# Custom_DUE.net
KiCad netlist of a schematic drawn in EAGLE
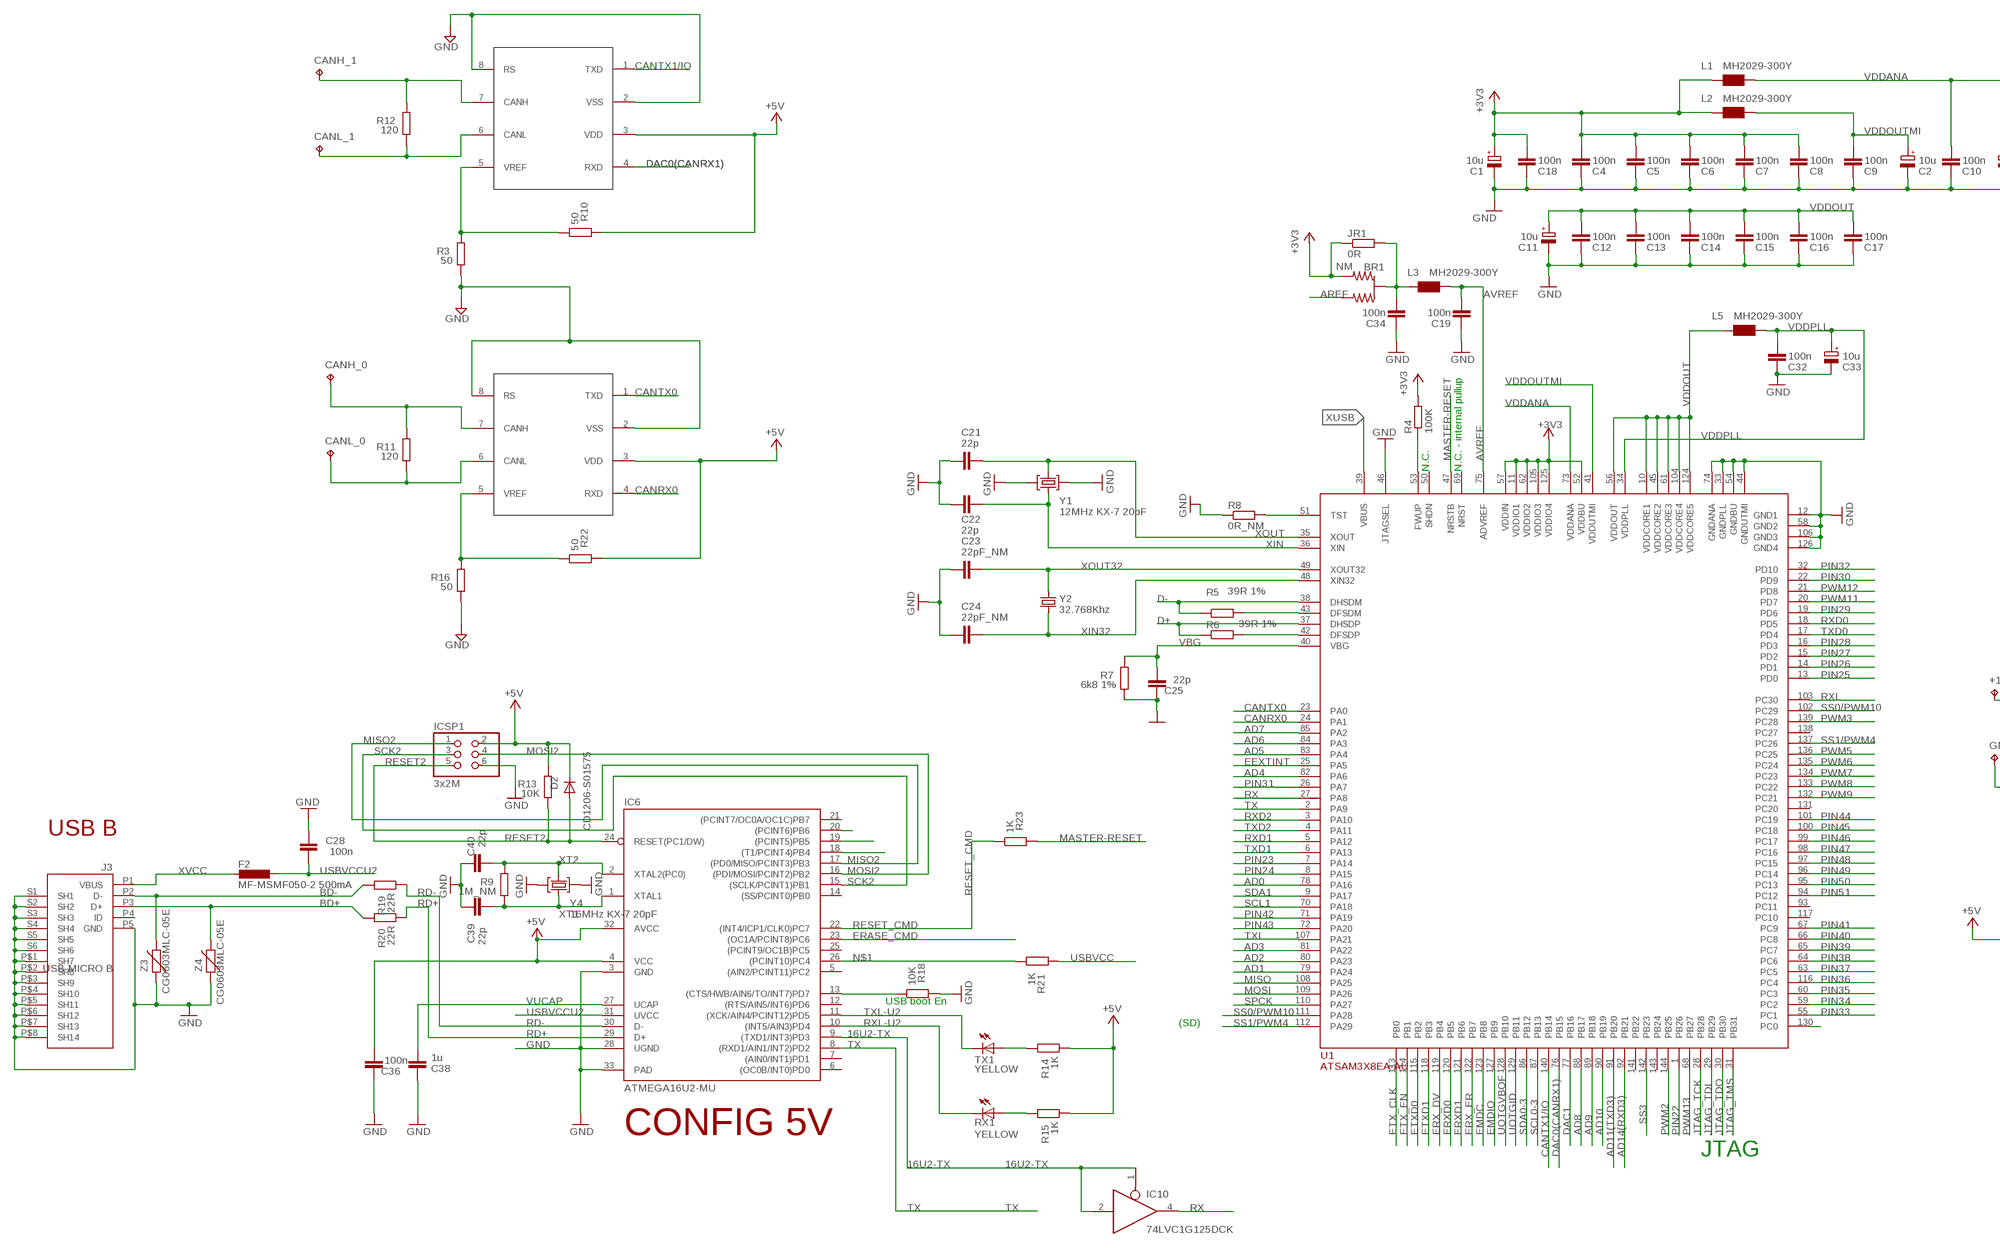
[diagram p0: schematic, sheet 1, part 1 of 2]
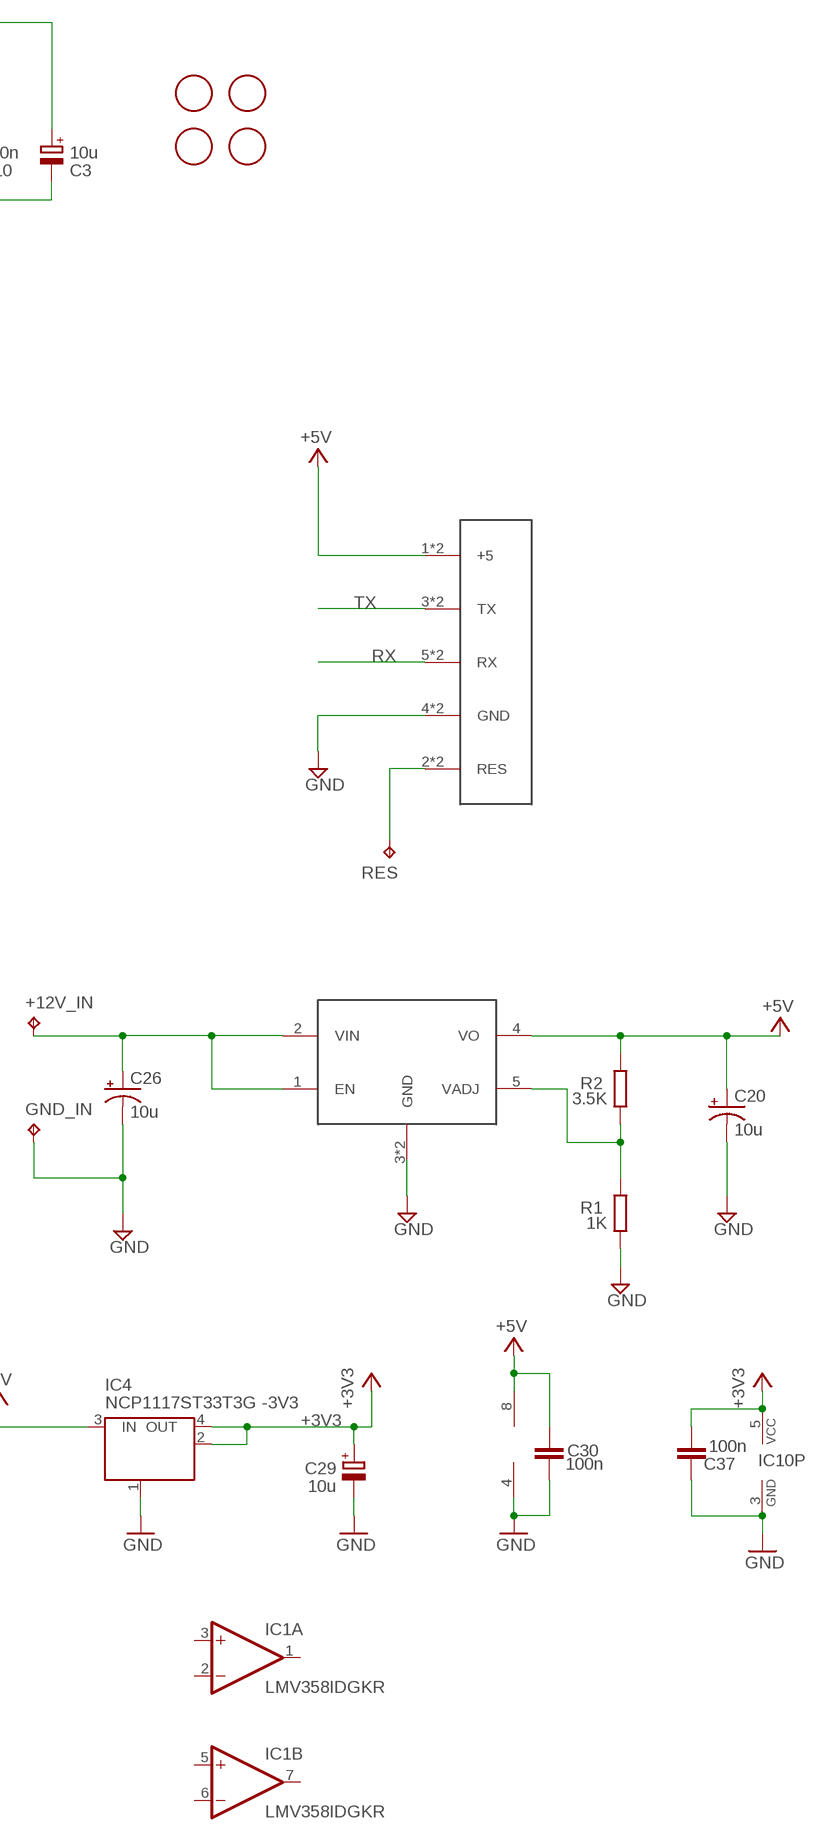
[diagram p1: schematic, sheet 1, part 2 of 2]

(export (version "E")
  (design (tool "Eeschema 10.0.6"))
  (components
    (comp (ref "+12V_IN")
      (value "TPPAD1-20")
      (footprint "eagle-import:P1-20")
      (libsource (lib "eagle-import") (part "TPPAD1-20"))
    )
    (comp (ref "BR1")
      (value "NM")
      (footprint "eagle-import:J0402")
      (libsource (lib "eagle-import") (part "J0402"))
    )
    (comp (ref "C1")
      (value "10u")
      (footprint "eagle-import:SMC_B")
      (libsource (lib "eagle-import") (part "CPOL-EUSMCB"))
    )
    (comp (ref "C2")
      (value "10u")
      (footprint "eagle-import:SMC_B")
      (libsource (lib "eagle-import") (part "CPOL-EUSMCB"))
    )
    (comp (ref "C3")
      (value "10u")
      (footprint "eagle-import:SMC_B")
      (libsource (lib "eagle-import") (part "CPOL-EUSMCB"))
    )
    (comp (ref "C4")
      (value "100n")
      (footprint "eagle-import:C0402")
      (libsource (lib "eagle-import") (part "C-EUC0402"))
    )
    (comp (ref "C5")
      (value "100n")
      (footprint "eagle-import:C0402")
      (libsource (lib "eagle-import") (part "C-EUC0402"))
    )
    (comp (ref "C6")
      (value "100n")
      (footprint "eagle-import:C0402")
      (libsource (lib "eagle-import") (part "C-EUC0402"))
    )
    (comp (ref "C7")
      (value "100n")
      (footprint "eagle-import:C0402")
      (libsource (lib "eagle-import") (part "C-EUC0402"))
    )
    (comp (ref "C8")
      (value "100n")
      (footprint "eagle-import:C0402")
      (libsource (lib "eagle-import") (part "C-EUC0402"))
    )
    (comp (ref "C9")
      (value "100n")
      (footprint "eagle-import:C0402")
      (libsource (lib "eagle-import") (part "C-EUC0402"))
    )
    (comp (ref "C10")
      (value "100n")
      (footprint "eagle-import:C0402")
      (libsource (lib "eagle-import") (part "C-EUC0402"))
    )
    (comp (ref "C11")
      (value "10u")
      (footprint "eagle-import:SMC_B")
      (libsource (lib "eagle-import") (part "CPOL-EUSMCB"))
    )
    (comp (ref "C12")
      (value "100n")
      (footprint "eagle-import:C0402")
      (libsource (lib "eagle-import") (part "C-EUC0402"))
    )
    (comp (ref "C13")
      (value "100n")
      (footprint "eagle-import:C0402")
      (libsource (lib "eagle-import") (part "C-EUC0402"))
    )
    (comp (ref "C14")
      (value "100n")
      (footprint "eagle-import:C0402")
      (libsource (lib "eagle-import") (part "C-EUC0402"))
    )
    (comp (ref "C15")
      (value "100n")
      (footprint "eagle-import:C0402")
      (libsource (lib "eagle-import") (part "C-EUC0402"))
    )
    (comp (ref "C16")
      (value "100n")
      (footprint "eagle-import:C0402")
      (libsource (lib "eagle-import") (part "C-EUC0402"))
    )
    (comp (ref "C17")
      (value "100n")
      (footprint "eagle-import:C0402")
      (libsource (lib "eagle-import") (part "C-EUC0402"))
    )
    (comp (ref "C18")
      (value "100n")
      (footprint "eagle-import:C0402")
      (libsource (lib "eagle-import") (part "C-EUC0402"))
    )
    (comp (ref "C19")
      (value "100n")
      (footprint "eagle-import:C0402")
      (libsource (lib "eagle-import") (part "C-EUC0402"))
    )
    (comp (ref "C20")
      (value "10u")
      (footprint "eagle-import:153CLV-0405")
      (libsource (lib "eagle-import") (part "CPOL-US153CLV-0405"))
    )
    (comp (ref "C21")
      (value "22p")
      (footprint "eagle-import:C0402")
      (libsource (lib "eagle-import") (part "C-EUC0402"))
    )
    (comp (ref "C22")
      (value "22p")
      (footprint "eagle-import:C0402")
      (libsource (lib "eagle-import") (part "C-EUC0402"))
    )
    (comp (ref "C23")
      (value "22pF_NM")
      (footprint "eagle-import:C0402")
      (libsource (lib "eagle-import") (part "C-EUC0402"))
    )
    (comp (ref "C24")
      (value "22pF_NM")
      (footprint "eagle-import:C0402")
      (libsource (lib "eagle-import") (part "C-EUC0402"))
    )
    (comp (ref "C25")
      (value "22p")
      (footprint "eagle-import:C0402")
      (libsource (lib "eagle-import") (part "C-EUC0402"))
    )
    (comp (ref "C26")
      (value "10u")
      (footprint "eagle-import:153CLV-0405")
      (libsource (lib "eagle-import") (part "CPOL-US153CLV-0405"))
    )
    (comp (ref "C28")
      (value "100n")
      (footprint "eagle-import:C0402")
      (libsource (lib "eagle-import") (part "C-EUC0402"))
    )
    (comp (ref "C29")
      (value "10u")
      (footprint "eagle-import:SMC_B")
      (libsource (lib "eagle-import") (part "CPOL-EUSMCB"))
    )
    (comp (ref "C30")
      (value "100n")
      (footprint "eagle-import:C0402")
      (libsource (lib "eagle-import") (part "C-EUC0402"))
    )
    (comp (ref "C32")
      (value "100n")
      (footprint "eagle-import:C0402")
      (libsource (lib "eagle-import") (part "C-EUC0402"))
    )
    (comp (ref "C33")
      (value "10u")
      (footprint "eagle-import:SMC_B")
      (libsource (lib "eagle-import") (part "CPOL-EUSMCB"))
    )
    (comp (ref "C34")
      (value "100n")
      (footprint "eagle-import:C0402")
      (libsource (lib "eagle-import") (part "C-EUC0402"))
    )
    (comp (ref "C36")
      (value "100n")
      (footprint "eagle-import:C0402")
      (libsource (lib "eagle-import") (part "C-EUC0402"))
    )
    (comp (ref "C37")
      (value "100n")
      (footprint "eagle-import:C0402")
      (libsource (lib "eagle-import") (part "C-EUC0402"))
    )
    (comp (ref "C38")
      (value "1u")
      (footprint "eagle-import:C0402")
      (libsource (lib "eagle-import") (part "C-EUC0402"))
    )
    (comp (ref "C39")
      (value "22p")
      (footprint "eagle-import:C0402")
      (libsource (lib "eagle-import") (part "C-EUC0402"))
    )
    (comp (ref "C40")
      (value "22p")
      (footprint "eagle-import:C0402")
      (libsource (lib "eagle-import") (part "C-EUC0402"))
    )
    (comp (ref "CANH_0")
      (value "TPPAD1-20")
      (footprint "eagle-import:P1-20")
      (libsource (lib "eagle-import") (part "TPPAD1-20"))
    )
    (comp (ref "CANH_1")
      (value "TPPAD1-20")
      (footprint "eagle-import:P1-20")
      (libsource (lib "eagle-import") (part "TPPAD1-20"))
    )
    (comp (ref "CANL_0")
      (value "TPPAD1-20")
      (footprint "eagle-import:P1-20")
      (libsource (lib "eagle-import") (part "TPPAD1-20"))
    )
    (comp (ref "CANL_1")
      (value "TPPAD1-20")
      (footprint "eagle-import:P1-20")
      (libsource (lib "eagle-import") (part "TPPAD1-20"))
    )
    (comp (ref "D2")
      (value "CD1206-S01575")
      (footprint "eagle-import:MINIMELF")
      (libsource (lib "eagle-import") (part "DIODE-MINIMELF"))
    )
    (comp (ref "F2")
      (value "MF-MSMF050-2 500mA")
      (footprint "eagle-import:L1812")
      (libsource (lib "eagle-import") (part "L-EUL1812"))
    )
    (comp (ref "FID1")
      (value "FIDUCIALMOUNT")
      (footprint "eagle-import:FIDUCIA-MOUNT")
      (libsource (lib "eagle-import") (part "FIDUCIALMOUNT"))
    )
    (comp (ref "FID2")
      (value "FIDUCIALMOUNT")
      (footprint "eagle-import:FIDUCIA-MOUNT")
      (libsource (lib "eagle-import") (part "FIDUCIALMOUNT"))
    )
    (comp (ref "FID3")
      (value "FIDUCIALMOUNT")
      (footprint "eagle-import:FIDUCIA-MOUNT")
      (libsource (lib "eagle-import") (part "FIDUCIALMOUNT"))
    )
    (comp (ref "FID4")
      (value "FIDUCIALMOUNT")
      (footprint "eagle-import:FIDUCIA-MOUNT")
      (libsource (lib "eagle-import") (part "FIDUCIALMOUNT"))
    )
    (comp (ref "GND_IN")
      (value "TPPAD1-20")
      (footprint "eagle-import:P1-20")
      (libsource (lib "eagle-import") (part "TPPAD1-20"))
    )
    (comp (ref "IC1")
      (value "LMV358IDGKR")
      (footprint "eagle-import:MSOP08")
      (libsource (lib "eagle-import") (part "LMV358?MMX"))
    )
    (comp (ref "IC4")
      (value "NCP1117ST33T3G -3V3")
      (footprint "eagle-import:SOT223")
      (libsource (lib "eagle-import") (part "MC33269ST-3.3T3"))
    )
    (comp (ref "IC6")
      (value "ATMEGA16U2-MU")
      (footprint "eagle-import:MLF32")
      (libsource (lib "eagle-import") (part "ATMEGA16U2-MU"))
    )
    (comp (ref "IC10")
      (value "74LVC1G125DCK")
      (footprint "eagle-import:SC70-5")
      (libsource (lib "eagle-import") (part "741G125DCKLVC"))
    )
    (comp (ref "ICSP1")
      (value "3x2M")
      (footprint "eagle-import:2X03")
      (libsource (lib "eagle-import") (part "PINHD-2X3"))
    )
    (comp (ref "J3")
      (value "USB-MICRO B")
      (footprint "eagle-import:CON2_USB_MICRO_B_AT")
      (libsource (lib "eagle-import") (part "MYCON2_USB-MINI-B"))
    )
    (comp (ref "JR1")
      (value "0R")
      (footprint "eagle-import:R0402")
      (libsource (lib "eagle-import") (part "R-EU_R0402"))
    )
    (comp (ref "L1")
      (value "MH2029-300Y")
      (footprint "eagle-import:0805")
      (libsource (lib "eagle-import") (part "WE-CBF_0805"))
    )
    (comp (ref "L2")
      (value "MH2029-300Y")
      (footprint "eagle-import:0805")
      (libsource (lib "eagle-import") (part "WE-CBF_0805"))
    )
    (comp (ref "L3")
      (value "MH2029-300Y")
      (footprint "eagle-import:0805")
      (libsource (lib "eagle-import") (part "WE-CBF_0805"))
    )
    (comp (ref "L5")
      (value "MH2029-300Y")
      (footprint "eagle-import:0805")
      (libsource (lib "eagle-import") (part "WE-CBF_0805"))
    )
    (comp (ref "R1")
      (value "1K")
      (footprint "eagle-import:R0402")
      (libsource (lib "eagle-import") (part "R-EU_R0402"))
    )
    (comp (ref "R2")
      (value "3.5K")
      (footprint "eagle-import:R0402")
      (libsource (lib "eagle-import") (part "R-EU_R0402"))
    )
    (comp (ref "R3")
      (value "50")
      (footprint "eagle-import:R0402")
      (libsource (lib "eagle-import") (part "R-EU_R0402"))
    )
    (comp (ref "R4")
      (value "100K")
      (footprint "eagle-import:R0402")
      (libsource (lib "eagle-import") (part "R-EU_R0402"))
    )
    (comp (ref "R5")
      (value "39R 1%")
      (footprint "eagle-import:R0402")
      (libsource (lib "eagle-import") (part "R-EU_R0402"))
    )
    (comp (ref "R6")
      (value "39R 1%")
      (footprint "eagle-import:R0402")
      (libsource (lib "eagle-import") (part "R-EU_R0402"))
    )
    (comp (ref "R7")
      (value "6k8 1%")
      (footprint "eagle-import:R0603-ROUND")
      (libsource (lib "eagle-import") (part "R-EU_R0603"))
    )
    (comp (ref "R8")
      (value "0R_NM")
      (footprint "eagle-import:R0402")
      (libsource (lib "eagle-import") (part "R-EU_R0402"))
    )
    (comp (ref "R9")
      (value "1M_NM")
      (footprint "eagle-import:R0402")
      (libsource (lib "eagle-import") (part "R-EU_R0402"))
    )
    (comp (ref "R10")
      (value "50")
      (footprint "eagle-import:R0402")
      (libsource (lib "eagle-import") (part "R-EU_R0402"))
    )
    (comp (ref "R11")
      (value "120")
      (footprint "eagle-import:R0402")
      (libsource (lib "eagle-import") (part "R-EU_R0402"))
    )
    (comp (ref "R12")
      (value "120")
      (footprint "eagle-import:R0402")
      (libsource (lib "eagle-import") (part "R-EU_R0402"))
    )
    (comp (ref "R13")
      (value "10K")
      (footprint "eagle-import:R0402")
      (libsource (lib "eagle-import") (part "R-EU_R0402"))
    )
    (comp (ref "R14")
      (value "1K")
      (footprint "eagle-import:R0402")
      (libsource (lib "eagle-import") (part "R-EU_R0402"))
    )
    (comp (ref "R15")
      (value "1K")
      (footprint "eagle-import:R0402")
      (libsource (lib "eagle-import") (part "R-EU_R0402"))
    )
    (comp (ref "R16")
      (value "50")
      (footprint "eagle-import:R0402")
      (libsource (lib "eagle-import") (part "R-EU_R0402"))
    )
    (comp (ref "R18")
      (value "10K")
      (footprint "eagle-import:R0402")
      (libsource (lib "eagle-import") (part "R-EU_R0402"))
    )
    (comp (ref "R19")
      (value "22R")
      (footprint "eagle-import:R0402")
      (libsource (lib "eagle-import") (part "R-EU_R0402"))
    )
    (comp (ref "R20")
      (value "22R")
      (footprint "eagle-import:R0402")
      (libsource (lib "eagle-import") (part "R-EU_R0402"))
    )
    (comp (ref "R21")
      (value "1K")
      (footprint "eagle-import:R0402")
      (libsource (lib "eagle-import") (part "R-EU_R0402"))
    )
    (comp (ref "R22")
      (value "50")
      (footprint "eagle-import:R0402")
      (libsource (lib "eagle-import") (part "R-EU_R0402"))
    )
    (comp (ref "R23")
      (value "1K")
      (footprint "eagle-import:R0402")
      (libsource (lib "eagle-import") (part "R-EU_R0402"))
    )
    (comp (ref "RES")
      (value "TPPAD1-20")
      (footprint "eagle-import:P1-20")
      (libsource (lib "eagle-import") (part "TPPAD1-20"))
    )
    (comp (ref "RX1")
      (value "YELLOW")
      (footprint "eagle-import:CHIP-LED0805")
      (libsource (lib "eagle-import") (part "LEDCHIP-LED0805"))
    )
    (comp (ref "TX1")
      (value "YELLOW")
      (footprint "eagle-import:CHIP-LED0805")
      (libsource (lib "eagle-import") (part "LEDCHIP-LED0805"))
    )
    (comp (ref "U$1")
      (value "TLF1963TBATMA1")
      (footprint "eagle-import:DPAK")
      (libsource (lib "eagle-import") (part "TLF1963"))
    )
    (comp (ref "U$3")
      (value "LCD_DISPLAY")
      (footprint "eagle-import:FE05-2")
      (libsource (lib "eagle-import") (part "LCD_DISPLAY"))
    )
    (comp (ref "U1")
      (value "ATSAM3X8EA-AU")
      (footprint "eagle-import:LQFP144")
      (libsource (lib "eagle-import") (part "ATSAM3X/AAU"))
    )
    (comp (ref "U2")
      (value "MCP2551")
      (footprint "eagle-import:SOIC8")
      (libsource (lib "eagle-import") (part "MCP2551"))
    )
    (comp (ref "U4")
      (value "MCP2551")
      (footprint "eagle-import:SOIC8")
      (libsource (lib "eagle-import") (part "MCP2551"))
    )
    (comp (ref "Y1")
      (value "12MHz KX-7 20pF")
      (footprint "eagle-import:CRYSTAL-3.2-2.5")
      (libsource (lib "eagle-import") (part "CRYSTAL-3.2-2.5"))
    )
    (comp (ref "Y2")
      (value "32.768Khz")
      (footprint "eagle-import:RESONATOR_EPSON_FC_145")
      (libsource (lib "eagle-import") (part "RESONATOR_EPSON_FC_145"))
    )
    (comp (ref "Y4")
      (value "16MHz KX-7 20pF")
      (footprint "eagle-import:CRYSTAL-3.2-2.5")
      (libsource (lib "eagle-import") (part "CRYSTAL-3.2-2.5"))
    )
    (comp (ref "Z3")
      (value "CG0603MLC-05E")
      (footprint "eagle-import:CT_CN0603")
      (libsource (lib "eagle-import") (part "VARISTORCN0603"))
    )
    (comp (ref "Z4")
      (value "CG0603MLC-05E")
      (footprint "eagle-import:CT_CN0603")
      (libsource (lib "eagle-import") (part "VARISTORCN0603"))
    )
  )
  (nets
    (net (code "1") (name "+3V3") (class "Default")
      (node (ref "BR1") (pin "3") (pinfunction "2_3") (pintype "passive"))
      (node (ref "C1") (pin "+") (pinfunction "+_+") (pintype "passive"))
      (node (ref "C18") (pin "2") (pinfunction "2_2") (pintype "passive"))
      (node (ref "C29") (pin "+") (pinfunction "+_+") (pintype "passive"))
      (node (ref "C37") (pin "1") (pinfunction "1_1") (pintype "passive"))
      (node (ref "C4") (pin "2") (pinfunction "2_2") (pintype "passive"))
      (node (ref "C5") (pin "2") (pinfunction "2_2") (pintype "passive"))
      (node (ref "C6") (pin "2") (pinfunction "2_2") (pintype "passive"))
      (node (ref "C7") (pin "2") (pinfunction "2_2") (pintype "passive"))
      (node (ref "C8") (pin "2") (pinfunction "2_2") (pintype "passive"))
      (node (ref "IC10") (pin "5") (pinfunction "VCC_5") (pintype "power_in"))
      (node (ref "IC4") (pin "2") (pinfunction "OUT_2") (pintype "passive"))
      (node (ref "IC4") (pin "4") (pinfunction "OUT_4") (pintype "passive"))
      (node (ref "JR1") (pin "1") (pinfunction "1_1") (pintype "passive"))
      (node (ref "L1") (pin "1") (pinfunction "1_1") (pintype "passive"))
      (node (ref "L2") (pin "1") (pinfunction "1_1") (pintype "passive"))
      (node (ref "R4") (pin "2") (pinfunction "2_2") (pintype "passive"))
      (node (ref "U1") (pin "105") (pinfunction "VDDIO3_105") (pintype "power_in"))
      (node (ref "U1") (pin "11") (pinfunction "VDDIO1_11") (pintype "power_in"))
      (node (ref "U1") (pin "125") (pinfunction "VDDIO4_125") (pintype "power_in"))
      (node (ref "U1") (pin "52") (pinfunction "VDDBU_52") (pintype "power_in"))
      (node (ref "U1") (pin "57") (pinfunction "VDDIN_57") (pintype "power_in"))
      (node (ref "U1") (pin "62") (pinfunction "VDDIO2_62") (pintype "power_in"))
    )
    (net (code "2") (name "+5V") (class "Default")
      (node (ref "C20") (pin "+") (pinfunction "+_+") (pintype "passive"))
      (node (ref "C30") (pin "2") (pinfunction "2_2") (pintype "passive"))
      (node (ref "C36") (pin "1") (pinfunction "1_1") (pintype "passive"))
      (node (ref "D2") (pin "C") (pinfunction "C_C") (pintype "passive"))
      (node (ref "IC1") (pin "8") (pinfunction "V+_8") (pintype "power_in"))
      (node (ref "IC4") (pin "3") (pinfunction "IN_3") (pintype "input"))
      (node (ref "IC6") (pin "32") (pinfunction "AVCC_32") (pintype "power_in"))
      (node (ref "IC6") (pin "4") (pinfunction "VCC_4") (pintype "power_in"))
      (node (ref "ICSP1") (pin "2") (pinfunction "2_2") (pintype "passive"))
      (node (ref "R10") (pin "2") (pinfunction "2_2") (pintype "passive"))
      (node (ref "R13") (pin "2") (pinfunction "2_2") (pintype "passive"))
      (node (ref "R14") (pin "1") (pinfunction "1_1") (pintype "passive"))
      (node (ref "R15") (pin "1") (pinfunction "1_1") (pintype "passive"))
      (node (ref "R2") (pin "2") (pinfunction "2_2") (pintype "passive"))
      (node (ref "R22") (pin "2") (pinfunction "2_2") (pintype "passive"))
      (node (ref "U$1") (pin "4") (pinfunction "VO_4") (pintype "bidirectional"))
      (node (ref "U$3") (pin "1") (pinfunction "+5_1") (pintype "bidirectional"))
      (node (ref "U$3") (pin "10") (pinfunction "+5_10") (pintype "bidirectional"))
      (node (ref "U2") (pin "3") (pinfunction "VDD_3") (pintype "bidirectional"))
      (node (ref "U4") (pin "3") (pinfunction "VDD_3") (pintype "bidirectional"))
    )
    (net (code "3") (name "/16U2-TX") (class "Default")
      (node (ref "IC10") (pin "1") (pinfunction "OE_1") (pintype "input"))
      (node (ref "IC10") (pin "2") (pinfunction "I_2") (pintype "input"))
      (node (ref "IC6") (pin "9") (pinfunction "(TXD1/INT3)PD3_9") (pintype "bidirectional"))
    )
    (net (code "4") (name "/AD0") (class "Default")
      (node (ref "U1") (pin "78") (pinfunction "PA16_78") (pintype "bidirectional"))
    )
    (net (code "5") (name "/AD1") (class "Default")
      (node (ref "U1") (pin "79") (pinfunction "PA24_79") (pintype "bidirectional"))
    )
    (net (code "6") (name "/AD2") (class "Default")
      (node (ref "U1") (pin "80") (pinfunction "PA23_80") (pintype "bidirectional"))
    )
    (net (code "7") (name "/AD3") (class "Default")
      (node (ref "U1") (pin "81") (pinfunction "PA22_81") (pintype "bidirectional"))
    )
    (net (code "8") (name "/AD4") (class "Default")
      (node (ref "U1") (pin "82") (pinfunction "PA6_82") (pintype "bidirectional"))
    )
    (net (code "9") (name "/AD5") (class "Default")
      (node (ref "U1") (pin "83") (pinfunction "PA4_83") (pintype "bidirectional"))
    )
    (net (code "10") (name "/AD6") (class "Default")
      (node (ref "U1") (pin "84") (pinfunction "PA3_84") (pintype "bidirectional"))
    )
    (net (code "11") (name "/AD7") (class "Default")
      (node (ref "U1") (pin "85") (pinfunction "PA2_85") (pintype "bidirectional"))
    )
    (net (code "12") (name "/AD8") (class "Default")
      (node (ref "U1") (pin "88") (pinfunction "PB17_88") (pintype "bidirectional"))
    )
    (net (code "13") (name "/AD9") (class "Default")
      (node (ref "U1") (pin "89") (pinfunction "PB18_89") (pintype "bidirectional"))
    )
    (net (code "14") (name "/AD10") (class "Default")
      (node (ref "U1") (pin "90") (pinfunction "PB19_90") (pintype "bidirectional"))
    )
    (net (code "15") (name "/AD11(TXD3)") (class "Default")
      (node (ref "U1") (pin "91") (pinfunction "PB20_91") (pintype "bidirectional"))
    )
    (net (code "16") (name "/AD14(RXD3)") (class "Default")
      (node (ref "U1") (pin "92") (pinfunction "PB21_92") (pintype "bidirectional"))
    )
    (net (code "17") (name "/AREF") (class "Default")
      (node (ref "BR1") (pin "1") (pinfunction "1_1") (pintype "passive"))
    )
    (net (code "18") (name "/AVREF") (class "Default")
      (node (ref "C19") (pin "2") (pinfunction "2_2") (pintype "passive"))
      (node (ref "L3") (pin "2") (pinfunction "2_2") (pintype "passive"))
      (node (ref "U1") (pin "75") (pinfunction "ADVREF_75") (pintype "power_in"))
    )
    (net (code "19") (name "/BD+") (class "Default")
      (node (ref "J3") (pin "P3") (pinfunction "D+_P3") (pintype "bidirectional"))
      (node (ref "R20") (pin "2") (pinfunction "2_2") (pintype "passive"))
      (node (ref "Z4") (pin "2") (pinfunction "2_2") (pintype "passive"))
    )
    (net (code "20") (name "/BD-") (class "Default")
      (node (ref "J3") (pin "P2") (pinfunction "D-_P2") (pintype "bidirectional"))
      (node (ref "R19") (pin "2") (pinfunction "2_2") (pintype "passive"))
      (node (ref "Z3") (pin "2") (pinfunction "2_2") (pintype "passive"))
    )
    (net (code "21") (name "/CANRX0") (class "Default")
      (node (ref "U1") (pin "24") (pinfunction "PA1_24") (pintype "bidirectional"))
      (node (ref "U4") (pin "4") (pinfunction "RXD_4") (pintype "bidirectional"))
    )
    (net (code "22") (name "/CANTX0") (class "Default")
      (node (ref "U1") (pin "23") (pinfunction "PA0_23") (pintype "bidirectional"))
      (node (ref "U4") (pin "1") (pinfunction "TXD_1") (pintype "bidirectional"))
    )
    (net (code "23") (name "/CANTX1{slash}IO") (class "Default")
      (node (ref "U1") (pin "140") (pinfunction "PB14_140") (pintype "bidirectional"))
      (node (ref "U2") (pin "1") (pinfunction "TXD_1") (pintype "bidirectional"))
    )
    (net (code "24") (name "/D+") (class "Default")
      (node (ref "R6") (pin "1") (pinfunction "1_1") (pintype "passive"))
      (node (ref "U1") (pin "37") (pinfunction "DHSDP_37") (pintype "bidirectional"))
    )
    (net (code "25") (name "/D-") (class "Default")
      (node (ref "R5") (pin "1") (pinfunction "1_1") (pintype "passive"))
      (node (ref "U1") (pin "38") (pinfunction "DHSDM_38") (pintype "bidirectional"))
    )
    (net (code "26") (name "/DAC0(CANRX1)") (class "Default")
      (node (ref "U1") (pin "76") (pinfunction "PB15_76") (pintype "bidirectional"))
      (node (ref "U2") (pin "4") (pinfunction "RXD_4") (pintype "bidirectional"))
    )
    (net (code "27") (name "/DAC1") (class "Default")
      (node (ref "U1") (pin "77") (pinfunction "PB16_77") (pintype "bidirectional"))
    )
    (net (code "28") (name "/EEXTINT") (class "Default")
      (node (ref "U1") (pin "25") (pinfunction "PA5_25") (pintype "bidirectional"))
    )
    (net (code "29") (name "/EMDC") (class "Default")
      (node (ref "U1") (pin "123") (pinfunction "PB8_123") (pintype "bidirectional"))
    )
    (net (code "30") (name "/EMDIO") (class "Default")
      (node (ref "U1") (pin "127") (pinfunction "PB9_127") (pintype "bidirectional"))
    )
    (net (code "31") (name "/ERASE_CMD") (class "Default")
      (node (ref "IC6") (pin "23") (pinfunction "(OC1A/PCINT8)PC6_23") (pintype "bidirectional"))
    )
    (net (code "32") (name "/ERXD0") (class "Default")
      (node (ref "U1") (pin "120") (pinfunction "PB5_120") (pintype "bidirectional"))
    )
    (net (code "33") (name "/ERXD1") (class "Default")
      (node (ref "U1") (pin "121") (pinfunction "PB6_121") (pintype "bidirectional"))
    )
    (net (code "34") (name "/ERX_DV") (class "Default")
      (node (ref "U1") (pin "119") (pinfunction "PB4_119") (pintype "bidirectional"))
    )
    (net (code "35") (name "/ERX_ER") (class "Default")
      (node (ref "U1") (pin "122") (pinfunction "PB7_122") (pintype "bidirectional"))
    )
    (net (code "36") (name "/ETXD0") (class "Default")
      (node (ref "U1") (pin "115") (pinfunction "PB2_115") (pintype "bidirectional"))
    )
    (net (code "37") (name "/ETXD1") (class "Default")
      (node (ref "U1") (pin "118") (pinfunction "PB3_118") (pintype "bidirectional"))
    )
    (net (code "38") (name "/ETX_CLK") (class "Default")
      (node (ref "U1") (pin "113") (pinfunction "PB0_113") (pintype "bidirectional"))
    )
    (net (code "39") (name "/ETX_EN") (class "Default")
      (node (ref "U1") (pin "114") (pinfunction "PB1_114") (pintype "bidirectional"))
    )
    (net (code "40") (name "/JTAG_TCK") (class "Default")
      (node (ref "U1") (pin "28") (pinfunction "PB28_28") (pintype "bidirectional"))
    )
    (net (code "41") (name "/JTAG_TDI") (class "Default")
      (node (ref "U1") (pin "29") (pinfunction "PB29_29") (pintype "bidirectional"))
    )
    (net (code "42") (name "/JTAG_TDO") (class "Default")
      (node (ref "U1") (pin "30") (pinfunction "PB30_30") (pintype "bidirectional"))
    )
    (net (code "43") (name "/JTAG_TMS") (class "Default")
      (node (ref "U1") (pin "31") (pinfunction "PB31_31") (pintype "bidirectional"))
    )
    (net (code "44") (name "/MASTER-RESET") (class "Default")
      (node (ref "R23") (pin "2") (pinfunction "2_2") (pintype "passive"))
      (node (ref "U1") (pin "47") (pinfunction "NRSTB_47") (pintype "input"))
    )
    (net (code "45") (name "/MISO") (class "Default")
      (node (ref "U1") (pin "108") (pinfunction "PA25_108") (pintype "bidirectional"))
    )
    (net (code "46") (name "/MISO2") (class "Default")
      (node (ref "IC6") (pin "17") (pinfunction "(PD0/MISO/PCINT3)PB3_17") (pintype "bidirectional"))
      (node (ref "ICSP1") (pin "1") (pinfunction "1_1") (pintype "passive"))
    )
    (net (code "47") (name "/MOSI") (class "Default")
      (node (ref "U1") (pin "109") (pinfunction "PA26_109") (pintype "bidirectional"))
    )
    (net (code "48") (name "/MOSI2") (class "Default")
      (node (ref "IC6") (pin "16") (pinfunction "(PDI/MOSI/PCINT2)PB2_16") (pintype "bidirectional"))
      (node (ref "ICSP1") (pin "4") (pinfunction "4_4") (pintype "passive"))
    )
    (net (code "49") (name "/N$1") (class "Default")
      (node (ref "IC6") (pin "26") (pinfunction "(PCINT10)PC4_26") (pintype "bidirectional"))
      (node (ref "R21") (pin "1") (pinfunction "1_1") (pintype "passive"))
    )
    (net (code "50") (name "/PIN22") (class "Default")
      (node (ref "U1") (pin "1") (pinfunction "PB26_1") (pintype "bidirectional"))
    )
    (net (code "51") (name "/PIN23") (class "Default")
      (node (ref "U1") (pin "7") (pinfunction "PA14_7") (pintype "bidirectional"))
    )
    (net (code "52") (name "/PIN24") (class "Default")
      (node (ref "U1") (pin "8") (pinfunction "PA15_8") (pintype "bidirectional"))
    )
    (net (code "53") (name "/PIN25") (class "Default")
      (node (ref "U1") (pin "13") (pinfunction "PD0_13") (pintype "bidirectional"))
    )
    (net (code "54") (name "/PIN26") (class "Default")
      (node (ref "U1") (pin "14") (pinfunction "PD1_14") (pintype "bidirectional"))
    )
    (net (code "55") (name "/PIN27") (class "Default")
      (node (ref "U1") (pin "15") (pinfunction "PD2_15") (pintype "bidirectional"))
    )
    (net (code "56") (name "/PIN28") (class "Default")
      (node (ref "U1") (pin "16") (pinfunction "PD3_16") (pintype "bidirectional"))
    )
    (net (code "57") (name "/PIN29") (class "Default")
      (node (ref "U1") (pin "19") (pinfunction "PD6_19") (pintype "bidirectional"))
    )
    (net (code "58") (name "/PIN30") (class "Default")
      (node (ref "U1") (pin "22") (pinfunction "PD9_22") (pintype "bidirectional"))
    )
    (net (code "59") (name "/PIN31") (class "Default")
      (node (ref "U1") (pin "26") (pinfunction "PA7_26") (pintype "bidirectional"))
    )
    (net (code "60") (name "/PIN32") (class "Default")
      (node (ref "U1") (pin "32") (pinfunction "PD10_32") (pintype "bidirectional"))
    )
    (net (code "61") (name "/PIN33") (class "Default")
      (node (ref "U1") (pin "55") (pinfunction "PC1_55") (pintype "bidirectional"))
    )
    (net (code "62") (name "/PIN34") (class "Default")
      (node (ref "U1") (pin "59") (pinfunction "PC2_59") (pintype "bidirectional"))
    )
    (net (code "63") (name "/PIN35") (class "Default")
      (node (ref "U1") (pin "60") (pinfunction "PC3_60") (pintype "bidirectional"))
    )
    (net (code "64") (name "/PIN36") (class "Default")
      (node (ref "U1") (pin "116") (pinfunction "PC4_116") (pintype "bidirectional"))
    )
    (net (code "65") (name "/PIN37") (class "Default")
      (node (ref "U1") (pin "63") (pinfunction "PC5_63") (pintype "bidirectional"))
    )
    (net (code "66") (name "/PIN38") (class "Default")
      (node (ref "U1") (pin "64") (pinfunction "PC6_64") (pintype "bidirectional"))
    )
    (net (code "67") (name "/PIN39") (class "Default")
      (node (ref "U1") (pin "65") (pinfunction "PC7_65") (pintype "bidirectional"))
    )
    (net (code "68") (name "/PIN40") (class "Default")
      (node (ref "U1") (pin "66") (pinfunction "PC8_66") (pintype "bidirectional"))
    )
    (net (code "69") (name "/PIN41") (class "Default")
      (node (ref "U1") (pin "67") (pinfunction "PC9_67") (pintype "bidirectional"))
    )
    (net (code "70") (name "/PIN42") (class "Default")
      (node (ref "U1") (pin "71") (pinfunction "PA19_71") (pintype "bidirectional"))
    )
    (net (code "71") (name "/PIN43") (class "Default")
      (node (ref "U1") (pin "72") (pinfunction "PA20_72") (pintype "bidirectional"))
    )
    (net (code "72") (name "/PIN44") (class "Default")
      (node (ref "U1") (pin "101") (pinfunction "PC19_101") (pintype "bidirectional"))
    )
    (net (code "73") (name "/PIN45") (class "Default")
      (node (ref "U1") (pin "100") (pinfunction "PC18_100") (pintype "bidirectional"))
    )
    (net (code "74") (name "/PIN46") (class "Default")
      (node (ref "U1") (pin "99") (pinfunction "PC17_99") (pintype "bidirectional"))
    )
    (net (code "75") (name "/PIN47") (class "Default")
      (node (ref "U1") (pin "98") (pinfunction "PC16_98") (pintype "bidirectional"))
    )
    (net (code "76") (name "/PIN48") (class "Default")
      (node (ref "U1") (pin "97") (pinfunction "PC15_97") (pintype "bidirectional"))
    )
    (net (code "77") (name "/PIN49") (class "Default")
      (node (ref "U1") (pin "96") (pinfunction "PC14_96") (pintype "bidirectional"))
    )
    (net (code "78") (name "/PIN50") (class "Default")
      (node (ref "U1") (pin "95") (pinfunction "PC13_95") (pintype "bidirectional"))
    )
    (net (code "79") (name "/PIN51") (class "Default")
      (node (ref "U1") (pin "94") (pinfunction "PC12_94") (pintype "bidirectional"))
    )
    (net (code "80") (name "/PWM2") (class "Default")
      (node (ref "U1") (pin "144") (pinfunction "PB25_144") (pintype "bidirectional"))
    )
    (net (code "81") (name "/PWM3") (class "Default")
      (node (ref "U1") (pin "139") (pinfunction "PC28_139") (pintype "bidirectional"))
    )
    (net (code "82") (name "/PWM5") (class "Default")
      (node (ref "U1") (pin "136") (pinfunction "PC25_136") (pintype "bidirectional"))
    )
    (net (code "83") (name "/PWM6") (class "Default")
      (node (ref "U1") (pin "135") (pinfunction "PC24_135") (pintype "bidirectional"))
    )
    (net (code "84") (name "/PWM7") (class "Default")
      (node (ref "U1") (pin "134") (pinfunction "PC23_134") (pintype "bidirectional"))
    )
    (net (code "85") (name "/PWM8") (class "Default")
      (node (ref "U1") (pin "133") (pinfunction "PC22_133") (pintype "bidirectional"))
    )
    (net (code "86") (name "/PWM9") (class "Default")
      (node (ref "U1") (pin "132") (pinfunction "PC21_132") (pintype "bidirectional"))
    )
    (net (code "87") (name "/PWM11") (class "Default")
      (node (ref "U1") (pin "20") (pinfunction "PD7_20") (pintype "bidirectional"))
    )
    (net (code "88") (name "/PWM12") (class "Default")
      (node (ref "U1") (pin "21") (pinfunction "PD8_21") (pintype "bidirectional"))
    )
    (net (code "89") (name "/PWM13") (class "Default")
      (node (ref "U1") (pin "68") (pinfunction "PB27_68") (pintype "bidirectional"))
    )
    (net (code "90") (name "/RD+") (class "Default")
      (node (ref "IC6") (pin "29") (pinfunction "D+_29") (pintype "bidirectional"))
      (node (ref "R20") (pin "1") (pinfunction "1_1") (pintype "passive"))
    )
    (net (code "91") (name "/RD-") (class "Default")
      (node (ref "IC6") (pin "30") (pinfunction "D-_30") (pintype "bidirectional"))
      (node (ref "R19") (pin "1") (pinfunction "1_1") (pintype "passive"))
    )
    (net (code "92") (name "/RESET2") (class "Default")
      (node (ref "D2") (pin "A") (pinfunction "A_A") (pintype "passive"))
      (node (ref "IC6") (pin "24") (pinfunction "RESET(PC1/DW)_24") (pintype "input"))
      (node (ref "ICSP1") (pin "5") (pinfunction "5_5") (pintype "passive"))
      (node (ref "R13") (pin "1") (pinfunction "1_1") (pintype "passive"))
    )
    (net (code "93") (name "/RESET_CMD") (class "Default")
      (node (ref "IC6") (pin "22") (pinfunction "(INT4/ICP1/CLK0)PC7_22") (pintype "bidirectional"))
      (node (ref "R23") (pin "1") (pinfunction "1_1") (pintype "passive"))
    )
    (net (code "94") (name "/RX") (class "Default")
      (node (ref "IC10") (pin "4") (pinfunction "O_4") (pintype "tri_state"))
      (node (ref "U$3") (pin "5") (pinfunction "RX_5") (pintype "bidirectional"))
      (node (ref "U$3") (pin "6") (pinfunction "RX_6") (pintype "bidirectional"))
      (node (ref "U1") (pin "27") (pinfunction "PA8_27") (pintype "bidirectional"))
    )
    (net (code "95") (name "/RXD0") (class "Default")
      (node (ref "U1") (pin "18") (pinfunction "PD5_18") (pintype "bidirectional"))
    )
    (net (code "96") (name "/RXD1") (class "Default")
      (node (ref "U1") (pin "5") (pinfunction "PA12_5") (pintype "bidirectional"))
    )
    (net (code "97") (name "/RXD2") (class "Default")
      (node (ref "U1") (pin "3") (pinfunction "PA10_3") (pintype "bidirectional"))
    )
    (net (code "98") (name "/RXL") (class "Default")
      (node (ref "U1") (pin "103") (pinfunction "PC30_103") (pintype "bidirectional"))
    )
    (net (code "99") (name "/RXL-U2") (class "Default")
      (node (ref "IC6") (pin "10") (pinfunction "(INT5/AIN3)PD4_10") (pintype "bidirectional"))
      (node (ref "RX1") (pin "C") (pinfunction "C_C") (pintype "passive"))
    )
    (net (code "100") (name "/SCK2") (class "Default")
      (node (ref "IC6") (pin "15") (pinfunction "(SCLK/PCINT1)PB1_15") (pintype "bidirectional"))
      (node (ref "ICSP1") (pin "3") (pinfunction "3_3") (pintype "passive"))
    )
    (net (code "101") (name "/SCL0-3") (class "Default")
      (node (ref "U1") (pin "87") (pinfunction "PB13_87") (pintype "bidirectional"))
    )
    (net (code "102") (name "/SCL1") (class "Default")
      (node (ref "U1") (pin "70") (pinfunction "PA18_70") (pintype "bidirectional"))
    )
    (net (code "103") (name "/SDA0-3") (class "Default")
      (node (ref "U1") (pin "86") (pinfunction "PB12_86") (pintype "bidirectional"))
    )
    (net (code "104") (name "/SDA1") (class "Default")
      (node (ref "U1") (pin "9") (pinfunction "PA17_9") (pintype "bidirectional"))
    )
    (net (code "105") (name "/SPCK") (class "Default")
      (node (ref "U1") (pin "110") (pinfunction "PA27_110") (pintype "bidirectional"))
    )
    (net (code "106") (name "/SS0{slash}PWM10") (class "Default")
      (node (ref "U1") (pin "102") (pinfunction "PC29_102") (pintype "bidirectional"))
      (node (ref "U1") (pin "111") (pinfunction "PA28_111") (pintype "bidirectional"))
    )
    (net (code "107") (name "/SS1{slash}PWM4") (class "Default")
      (node (ref "U1") (pin "112") (pinfunction "PA29_112") (pintype "bidirectional"))
      (node (ref "U1") (pin "137") (pinfunction "PC26_137") (pintype "bidirectional"))
    )
    (net (code "108") (name "/SS3") (class "Default")
      (node (ref "U1") (pin "142") (pinfunction "PB23_142") (pintype "bidirectional"))
    )
    (net (code "109") (name "/TX") (class "Default")
      (node (ref "IC6") (pin "8") (pinfunction "(RXD1/AIN1/INT2)PD2_8") (pintype "bidirectional"))
      (node (ref "U$3") (pin "3") (pinfunction "TX_3") (pintype "bidirectional"))
      (node (ref "U$3") (pin "8") (pinfunction "TX_8") (pintype "bidirectional"))
      (node (ref "U1") (pin "2") (pinfunction "PA9_2") (pintype "bidirectional"))
    )
    (net (code "110") (name "/TXD0") (class "Default")
      (node (ref "U1") (pin "17") (pinfunction "PD4_17") (pintype "bidirectional"))
    )
    (net (code "111") (name "/TXD1") (class "Default")
      (node (ref "U1") (pin "6") (pinfunction "PA13_6") (pintype "bidirectional"))
    )
    (net (code "112") (name "/TXD2") (class "Default")
      (node (ref "U1") (pin "4") (pinfunction "PA11_4") (pintype "bidirectional"))
    )
    (net (code "113") (name "/TXL") (class "Default")
      (node (ref "U1") (pin "107") (pinfunction "PA21_107") (pintype "bidirectional"))
    )
    (net (code "114") (name "/TXL-U2") (class "Default")
      (node (ref "IC6") (pin "11") (pinfunction "(XCK/AIN4/PCINT12)PD5_11") (pintype "bidirectional"))
      (node (ref "TX1") (pin "C") (pinfunction "C_C") (pintype "passive"))
    )
    (net (code "115") (name "/UOTGID") (class "Default")
      (node (ref "U1") (pin "129") (pinfunction "PB11_129") (pintype "bidirectional"))
    )
    (net (code "116") (name "/UOTGVBOF") (class "Default")
      (node (ref "U1") (pin "128") (pinfunction "PB10_128") (pintype "bidirectional"))
    )
    (net (code "117") (name "/USBVCC") (class "Default")
      (node (ref "R21") (pin "2") (pinfunction "2_2") (pintype "passive"))
    )
    (net (code "118") (name "/USBVCCU2") (class "Default")
      (node (ref "C28") (pin "1") (pinfunction "1_1") (pintype "passive"))
      (node (ref "F2") (pin "1") (pinfunction "1_1") (pintype "passive"))
      (node (ref "IC6") (pin "31") (pinfunction "UVCC_31") (pintype "power_in"))
    )
    (net (code "119") (name "/VBG") (class "Default")
      (node (ref "C25") (pin "1") (pinfunction "1_1") (pintype "passive"))
      (node (ref "R7") (pin "2") (pinfunction "2_2") (pintype "passive"))
      (node (ref "U1") (pin "40") (pinfunction "VBG_40") (pintype "passive"))
    )
    (net (code "120") (name "/VDDANA") (class "Default")
      (node (ref "C10") (pin "2") (pinfunction "2_2") (pintype "passive"))
      (node (ref "C3") (pin "+") (pinfunction "+_+") (pintype "passive"))
      (node (ref "L1") (pin "2") (pinfunction "2_2") (pintype "passive"))
      (node (ref "U1") (pin "73") (pinfunction "VDDANA_73") (pintype "power_in"))
    )
    (net (code "121") (name "/VDDOUT") (class "Default")
      (node (ref "C11") (pin "+") (pinfunction "+_+") (pintype "passive"))
      (node (ref "C12") (pin "2") (pinfunction "2_2") (pintype "passive"))
      (node (ref "C13") (pin "2") (pinfunction "2_2") (pintype "passive"))
      (node (ref "C14") (pin "2") (pinfunction "2_2") (pintype "passive"))
      (node (ref "C15") (pin "2") (pinfunction "2_2") (pintype "passive"))
      (node (ref "C16") (pin "2") (pinfunction "2_2") (pintype "passive"))
      (node (ref "C17") (pin "2") (pinfunction "2_2") (pintype "passive"))
      (node (ref "L5") (pin "1") (pinfunction "1_1") (pintype "passive"))
      (node (ref "U1") (pin "10") (pinfunction "VDDCORE1_10") (pintype "input"))
      (node (ref "U1") (pin "104") (pinfunction "VDDCORE4_104") (pintype "input"))
      (node (ref "U1") (pin "124") (pinfunction "VDDCORE5_124") (pintype "input"))
      (node (ref "U1") (pin "45") (pinfunction "VDDCORE2_45") (pintype "input"))
      (node (ref "U1") (pin "56") (pinfunction "VDDOUT_56") (pintype "output"))
      (node (ref "U1") (pin "61") (pinfunction "VDDCORE3_61") (pintype "input"))
    )
    (net (code "122") (name "/VDDOUTMI") (class "Default")
      (node (ref "C2") (pin "+") (pinfunction "+_+") (pintype "passive"))
      (node (ref "C9") (pin "2") (pinfunction "2_2") (pintype "passive"))
      (node (ref "L2") (pin "2") (pinfunction "2_2") (pintype "passive"))
      (node (ref "U1") (pin "41") (pinfunction "VDDUTMI_41") (pintype "input"))
    )
    (net (code "123") (name "/VDDPLL") (class "Default")
      (node (ref "C32") (pin "2") (pinfunction "2_2") (pintype "passive"))
      (node (ref "C33") (pin "+") (pinfunction "+_+") (pintype "passive"))
      (node (ref "L5") (pin "2") (pinfunction "2_2") (pintype "passive"))
      (node (ref "U1") (pin "34") (pinfunction "VDDPLL_34") (pintype "input"))
    )
    (net (code "124") (name "/VUCAP") (class "Default")
      (node (ref "C38") (pin "1") (pinfunction "1_1") (pintype "passive"))
      (node (ref "IC6") (pin "27") (pinfunction "UCAP_27") (pintype "passive"))
    )
    (net (code "125") (name "/XIN") (class "Default")
      (node (ref "C22") (pin "1") (pinfunction "1_1") (pintype "passive"))
      (node (ref "U1") (pin "36") (pinfunction "XIN_36") (pintype "input"))
      (node (ref "Y1") (pin "1") (pinfunction "C1_1") (pintype "passive"))
    )
    (net (code "126") (name "/XIN32") (class "Default")
      (node (ref "C24") (pin "1") (pinfunction "1_1") (pintype "passive"))
      (node (ref "U1") (pin "48") (pinfunction "XIN32_48") (pintype "output"))
      (node (ref "Y2") (pin "P$2") (pinfunction "2_P$2") (pintype "bidirectional"))
    )
    (net (code "127") (name "/XOUT") (class "Default")
      (node (ref "C21") (pin "1") (pinfunction "1_1") (pintype "passive"))
      (node (ref "U1") (pin "35") (pinfunction "XOUT_35") (pintype "output"))
      (node (ref "Y1") (pin "3") (pinfunction "C2_3") (pintype "passive"))
    )
    (net (code "128") (name "/XOUT32") (class "Default")
      (node (ref "C23") (pin "1") (pinfunction "1_1") (pintype "passive"))
      (node (ref "U1") (pin "49") (pinfunction "XOUT32_49") (pintype "output"))
      (node (ref "Y2") (pin "P$1") (pinfunction "1_P$1") (pintype "bidirectional"))
    )
    (net (code "129") (name "/XT1") (class "Default")
      (node (ref "C39") (pin "1") (pinfunction "1_1") (pintype "passive"))
      (node (ref "IC6") (pin "1") (pinfunction "XTAL1_1") (pintype "bidirectional"))
      (node (ref "R9") (pin "1") (pinfunction "1_1") (pintype "passive"))
      (node (ref "Y4") (pin "1") (pinfunction "C1_1") (pintype "passive"))
    )
    (net (code "130") (name "/XT2") (class "Default")
      (node (ref "C40") (pin "1") (pinfunction "1_1") (pintype "passive"))
      (node (ref "IC6") (pin "2") (pinfunction "XTAL2(PC0)_2") (pintype "bidirectional"))
      (node (ref "R9") (pin "2") (pinfunction "2_2") (pintype "passive"))
      (node (ref "Y4") (pin "3") (pinfunction "C2_3") (pintype "passive"))
    )
    (net (code "131") (name "/XVCC") (class "Default")
      (node (ref "F2") (pin "2") (pinfunction "2_2") (pintype "passive"))
      (node (ref "J3") (pin "P1") (pinfunction "VBUS_P1") (pintype "power_in"))
    )
    (net (code "132") (name "GND") (class "Default")
      (node (ref "C1") (pin "-") (pinfunction "-_-") (pintype "passive"))
      (node (ref "C10") (pin "1") (pinfunction "1_1") (pintype "passive"))
      (node (ref "C11") (pin "-") (pinfunction "-_-") (pintype "passive"))
      (node (ref "C12") (pin "1") (pinfunction "1_1") (pintype "passive"))
      (node (ref "C13") (pin "1") (pinfunction "1_1") (pintype "passive"))
      (node (ref "C14") (pin "1") (pinfunction "1_1") (pintype "passive"))
      (node (ref "C15") (pin "1") (pinfunction "1_1") (pintype "passive"))
      (node (ref "C16") (pin "1") (pinfunction "1_1") (pintype "passive"))
      (node (ref "C17") (pin "1") (pinfunction "1_1") (pintype "passive"))
      (node (ref "C18") (pin "1") (pinfunction "1_1") (pintype "passive"))
      (node (ref "C19") (pin "1") (pinfunction "1_1") (pintype "passive"))
      (node (ref "C2") (pin "-") (pinfunction "-_-") (pintype "passive"))
      (node (ref "C20") (pin "-") (pinfunction "-_-") (pintype "passive"))
      (node (ref "C21") (pin "2") (pinfunction "2_2") (pintype "passive"))
      (node (ref "C22") (pin "2") (pinfunction "2_2") (pintype "passive"))
      (node (ref "C23") (pin "2") (pinfunction "2_2") (pintype "passive"))
      (node (ref "C24") (pin "2") (pinfunction "2_2") (pintype "passive"))
      (node (ref "C25") (pin "2") (pinfunction "2_2") (pintype "passive"))
      (node (ref "C26") (pin "-") (pinfunction "-_-") (pintype "passive"))
      (node (ref "C28") (pin "2") (pinfunction "2_2") (pintype "passive"))
      (node (ref "C29") (pin "-") (pinfunction "-_-") (pintype "passive"))
      (node (ref "C3") (pin "-") (pinfunction "-_-") (pintype "passive"))
      (node (ref "C30") (pin "1") (pinfunction "1_1") (pintype "passive"))
      (node (ref "C32") (pin "1") (pinfunction "1_1") (pintype "passive"))
      (node (ref "C33") (pin "-") (pinfunction "-_-") (pintype "passive"))
      (node (ref "C34") (pin "1") (pinfunction "1_1") (pintype "passive"))
      (node (ref "C36") (pin "2") (pinfunction "2_2") (pintype "passive"))
      (node (ref "C37") (pin "2") (pinfunction "2_2") (pintype "passive"))
      (node (ref "C38") (pin "2") (pinfunction "2_2") (pintype "passive"))
      (node (ref "C39") (pin "2") (pinfunction "2_2") (pintype "passive"))
      (node (ref "C4") (pin "1") (pinfunction "1_1") (pintype "passive"))
      (node (ref "C40") (pin "2") (pinfunction "2_2") (pintype "passive"))
      (node (ref "C5") (pin "1") (pinfunction "1_1") (pintype "passive"))
      (node (ref "C6") (pin "1") (pinfunction "1_1") (pintype "passive"))
      (node (ref "C7") (pin "1") (pinfunction "1_1") (pintype "passive"))
      (node (ref "C8") (pin "1") (pinfunction "1_1") (pintype "passive"))
      (node (ref "C9") (pin "1") (pinfunction "1_1") (pintype "passive"))
      (node (ref "GND_IN") (pin "TP") (pinfunction "TP_TP") (pintype "input"))
      (node (ref "IC1") (pin "4") (pinfunction "V-_4") (pintype "power_in"))
      (node (ref "IC10") (pin "3") (pinfunction "GND_3") (pintype "power_in"))
      (node (ref "IC4") (pin "1") (pinfunction "GND/ADJ_1") (pintype "input"))
      (node (ref "IC6") (pin "28") (pinfunction "UGND_28") (pintype "power_in"))
      (node (ref "IC6") (pin "3") (pinfunction "GND_3") (pintype "power_in"))
      (node (ref "IC6") (pin "33") (pinfunction "PAD_33") (pintype "power_in"))
      (node (ref "ICSP1") (pin "6") (pinfunction "6_6") (pintype "passive"))
      (node (ref "J3") (pin "P$1") (pinfunction "SH7_P$1") (pintype "passive"))
      (node (ref "J3") (pin "P$2") (pinfunction "SH8_P$2") (pintype "passive"))
      (node (ref "J3") (pin "P$3") (pinfunction "SH9_P$3") (pintype "passive"))
      (node (ref "J3") (pin "P$4") (pinfunction "SH10_P$4") (pintype "passive"))
      (node (ref "J3") (pin "P$5") (pinfunction "SH11_P$5") (pintype "passive"))
      (node (ref "J3") (pin "P$6") (pinfunction "SH12_P$6") (pintype "passive"))
      (node (ref "J3") (pin "P$7") (pinfunction "SH13_P$7") (pintype "passive"))
      (node (ref "J3") (pin "P$8") (pinfunction "SH14_P$8") (pintype "passive"))
      (node (ref "J3") (pin "P5") (pinfunction "GND_P5") (pintype "passive"))
      (node (ref "J3") (pin "S1") (pinfunction "SH1_S1") (pintype "passive"))
      (node (ref "J3") (pin "S2") (pinfunction "SH2_S2") (pintype "passive"))
      (node (ref "J3") (pin "S3") (pinfunction "SH3_S3") (pintype "passive"))
      (node (ref "J3") (pin "S4") (pinfunction "SH4_S4") (pintype "passive"))
      (node (ref "J3") (pin "S5") (pinfunction "SH5_S5") (pintype "passive"))
      (node (ref "J3") (pin "S6") (pinfunction "SH6_S6") (pintype "passive"))
      (node (ref "R1") (pin "1") (pinfunction "1_1") (pintype "passive"))
      (node (ref "R16") (pin "1") (pinfunction "1_1") (pintype "passive"))
      (node (ref "R18") (pin "2") (pinfunction "2_2") (pintype "passive"))
      (node (ref "R3") (pin "1") (pinfunction "1_1") (pintype "passive"))
      (node (ref "R7") (pin "1") (pinfunction "1_1") (pintype "passive"))
      (node (ref "R8") (pin "1") (pinfunction "1_1") (pintype "passive"))
      (node (ref "U$1") (pin "3") (pinfunction "GND_3") (pintype "bidirectional"))
      (node (ref "U$1") (pin "6") (pinfunction "GND_6") (pintype "bidirectional"))
      (node (ref "U$3") (pin "4") (pinfunction "GND_4") (pintype "bidirectional"))
      (node (ref "U$3") (pin "7") (pinfunction "GND_7") (pintype "bidirectional"))
      (node (ref "U1") (pin "106") (pinfunction "GND3_106") (pintype "power_in"))
      (node (ref "U1") (pin "12") (pinfunction "GND1_12") (pintype "power_in"))
      (node (ref "U1") (pin "126") (pinfunction "GND4_126") (pintype "power_in"))
      (node (ref "U1") (pin "33") (pinfunction "GNDPLL_33") (pintype "power_in"))
      (node (ref "U1") (pin "44") (pinfunction "GNDUTMI_44") (pintype "power_in"))
      (node (ref "U1") (pin "46") (pinfunction "JTAGSEL_46") (pintype "input"))
      (node (ref "U1") (pin "54") (pinfunction "GNDBU_54") (pintype "power_in"))
      (node (ref "U1") (pin "58") (pinfunction "GND2_58") (pintype "power_in"))
      (node (ref "U1") (pin "74") (pinfunction "GNDANA_74") (pintype "power_in"))
      (node (ref "U2") (pin "2") (pinfunction "VSS_2") (pintype "bidirectional"))
      (node (ref "U2") (pin "8") (pinfunction "RS_8") (pintype "bidirectional"))
      (node (ref "U4") (pin "2") (pinfunction "VSS_2") (pintype "bidirectional"))
      (node (ref "U4") (pin "8") (pinfunction "RS_8") (pintype "bidirectional"))
      (node (ref "Y1") (pin "2") (pinfunction "GND_2") (pintype "passive"))
      (node (ref "Y1") (pin "4") (pinfunction "GND_4") (pintype "passive"))
      (node (ref "Y4") (pin "2") (pinfunction "GND_2") (pintype "passive"))
      (node (ref "Y4") (pin "4") (pinfunction "GND_4") (pintype "passive"))
      (node (ref "Z3") (pin "1") (pinfunction "1_1") (pintype "passive"))
      (node (ref "Z4") (pin "1") (pinfunction "1_1") (pintype "passive"))
    )
    (net (code "133") (name "Net-(BR1-C)") (class "Default")
      (node (ref "BR1") (pin "2") (pinfunction "C_2") (pintype "passive"))
      (node (ref "C34") (pin "2") (pinfunction "2_2") (pintype "passive"))
      (node (ref "JR1") (pin "2") (pinfunction "2_2") (pintype "passive"))
      (node (ref "L3") (pin "1") (pinfunction "1_1") (pintype "passive"))
    )
    (net (code "134") (name "Net-(IC6-(CTS{slash}HWB{slash}AIN6{slash}TO{slash}INT7)PD7)") (class "Default")
      (node (ref "IC6") (pin "13") (pinfunction "(CTS/HWB/AIN6/TO/INT7)PD7_13") (pintype "bidirectional"))
      (node (ref "R18") (pin "1") (pinfunction "1_1") (pintype "passive"))
    )
    (net (code "135") (name "Net-(R14-Pad2)") (class "Default")
      (node (ref "R14") (pin "2") (pinfunction "2_2") (pintype "passive"))
      (node (ref "TX1") (pin "A") (pinfunction "A_A") (pintype "passive"))
    )
    (net (code "136") (name "Net-(R15-Pad2)") (class "Default")
      (node (ref "R15") (pin "2") (pinfunction "2_2") (pintype "passive"))
      (node (ref "RX1") (pin "A") (pinfunction "A_A") (pintype "passive"))
    )
    (net (code "137") (name "Net-(RES-PadTP)") (class "Default")
      (node (ref "RES") (pin "TP") (pinfunction "TP_TP") (pintype "input"))
      (node (ref "U$3") (pin "2") (pinfunction "RES_2") (pintype "bidirectional"))
      (node (ref "U$3") (pin "9") (pinfunction "RES_9") (pintype "bidirectional"))
    )
    (net (code "138") (name "Net-(U$1-EN)") (class "Default")
      (node (ref "+12V_IN") (pin "TP") (pinfunction "TP_TP") (pintype "input"))
      (node (ref "C26") (pin "+") (pinfunction "+_+") (pintype "passive"))
      (node (ref "U$1") (pin "1") (pinfunction "EN_1") (pintype "bidirectional"))
      (node (ref "U$1") (pin "2") (pinfunction "VIN_2") (pintype "bidirectional"))
    )
    (net (code "139") (name "Net-(U$1-VADJ)") (class "Default")
      (node (ref "R1") (pin "2") (pinfunction "2_2") (pintype "passive"))
      (node (ref "R2") (pin "1") (pinfunction "1_1") (pintype "passive"))
      (node (ref "U$1") (pin "5") (pinfunction "VADJ_5") (pintype "bidirectional"))
    )
    (net (code "140") (name "Net-(U1-DFSDM)") (class "Default")
      (node (ref "R5") (pin "2") (pinfunction "2_2") (pintype "passive"))
      (node (ref "U1") (pin "43") (pinfunction "DFSDM_43") (pintype "input"))
    )
    (net (code "141") (name "Net-(U1-DFSDP)") (class "Default")
      (node (ref "R6") (pin "2") (pinfunction "2_2") (pintype "passive"))
      (node (ref "U1") (pin "42") (pinfunction "DFSDP_42") (pintype "input"))
    )
    (net (code "142") (name "Net-(U1-FWUP)") (class "Default")
      (node (ref "R4") (pin "1") (pinfunction "1_1") (pintype "passive"))
      (node (ref "U1") (pin "53") (pinfunction "FWUP_53") (pintype "input"))
    )
    (net (code "143") (name "Net-(U1-TST)") (class "Default")
      (node (ref "R8") (pin "2") (pinfunction "2_2") (pintype "passive"))
      (node (ref "U1") (pin "51") (pinfunction "TST_51") (pintype "input"))
    )
    (net (code "144") (name "Net-(U2-CANH)") (class "Default")
      (node (ref "CANH_1") (pin "TP") (pinfunction "TP_TP") (pintype "input"))
      (node (ref "R12") (pin "2") (pinfunction "2_2") (pintype "passive"))
      (node (ref "U2") (pin "7") (pinfunction "CANH_7") (pintype "bidirectional"))
    )
    (net (code "145") (name "Net-(U2-CANL)") (class "Default")
      (node (ref "CANL_1") (pin "TP") (pinfunction "TP_TP") (pintype "input"))
      (node (ref "R12") (pin "1") (pinfunction "1_1") (pintype "passive"))
      (node (ref "U2") (pin "6") (pinfunction "CANL_6") (pintype "bidirectional"))
    )
    (net (code "146") (name "Net-(U2-VREF)") (class "Default")
      (node (ref "R10") (pin "1") (pinfunction "1_1") (pintype "passive"))
      (node (ref "R3") (pin "2") (pinfunction "2_2") (pintype "passive"))
      (node (ref "U2") (pin "5") (pinfunction "VREF_5") (pintype "bidirectional"))
    )
    (net (code "147") (name "Net-(U4-CANH)") (class "Default")
      (node (ref "CANH_0") (pin "TP") (pinfunction "TP_TP") (pintype "input"))
      (node (ref "R11") (pin "2") (pinfunction "2_2") (pintype "passive"))
      (node (ref "U4") (pin "7") (pinfunction "CANH_7") (pintype "bidirectional"))
    )
    (net (code "148") (name "Net-(U4-CANL)") (class "Default")
      (node (ref "CANL_0") (pin "TP") (pinfunction "TP_TP") (pintype "input"))
      (node (ref "R11") (pin "1") (pinfunction "1_1") (pintype "passive"))
      (node (ref "U4") (pin "6") (pinfunction "CANL_6") (pintype "bidirectional"))
    )
    (net (code "149") (name "Net-(U4-VREF)") (class "Default")
      (node (ref "R16") (pin "2") (pinfunction "2_2") (pintype "passive"))
      (node (ref "R22") (pin "1") (pinfunction "1_1") (pintype "passive"))
      (node (ref "U4") (pin "5") (pinfunction "VREF_5") (pintype "bidirectional"))
    )
    (net (code "150") (name "XUSB") (class "Default")
      (node (ref "U1") (pin "39") (pinfunction "VBUS_39") (pintype "power_in"))
    )
    (net (code "151") (name "unconnected-(IC1A-+IN-Pad3)") (class "Default")
      (node (ref "IC1") (pin "3") (pinfunction "+IN_3") (pintype "input"))
    )
    (net (code "152") (name "unconnected-(IC1A--IN-Pad2)") (class "Default")
      (node (ref "IC1") (pin "2") (pinfunction "-IN_2") (pintype "input"))
    )
    (net (code "153") (name "unconnected-(IC1A-OUT-Pad1)") (class "Default")
      (node (ref "IC1") (pin "1") (pinfunction "OUT_1") (pintype "output"))
    )
    (net (code "154") (name "unconnected-(IC1B-+IN-Pad5)") (class "Default")
      (node (ref "IC1") (pin "5") (pinfunction "+IN_5") (pintype "input"))
    )
    (net (code "155") (name "unconnected-(IC1B--IN-Pad6)") (class "Default")
      (node (ref "IC1") (pin "6") (pinfunction "-IN_6") (pintype "input"))
    )
    (net (code "156") (name "unconnected-(IC1B-OUT-Pad7)") (class "Default")
      (node (ref "IC1") (pin "7") (pinfunction "OUT_7") (pintype "output"))
    )
    (net (code "157") (name "unconnected-(IC6-(AIN0{slash}INT1)PD1-Pad7)") (class "Default")
      (node (ref "IC6") (pin "7") (pinfunction "(AIN0/INT1)PD1_7") (pintype "bidirectional"))
    )
    (net (code "158") (name "unconnected-(IC6-(AIN2{slash}PCINT11)PC2-Pad5)") (class "Default")
      (node (ref "IC6") (pin "5") (pinfunction "(AIN2/PCINT11)PC2_5") (pintype "bidirectional"))
    )
    (net (code "159") (name "unconnected-(IC6-(OC0B{slash}INT0)PD0-Pad6)") (class "Default")
      (node (ref "IC6") (pin "6") (pinfunction "(OC0B/INT0)PD0_6") (pintype "bidirectional"))
    )
    (net (code "160") (name "unconnected-(IC6-(PCINT5)PB5-Pad19)") (class "Default")
      (node (ref "IC6") (pin "19") (pinfunction "(PCINT5)PB5_19") (pintype "bidirectional"))
    )
    (net (code "161") (name "unconnected-(IC6-(PCINT6)PB6-Pad20)") (class "Default")
      (node (ref "IC6") (pin "20") (pinfunction "(PCINT6)PB6_20") (pintype "bidirectional"))
    )
    (net (code "162") (name "unconnected-(IC6-(PCINT7{slash}OC0A{slash}OC1C)PB7-Pad21)") (class "Default")
      (node (ref "IC6") (pin "21") (pinfunction "(PCINT7/OC0A/OC1C)PB7_21") (pintype "bidirectional"))
    )
    (net (code "163") (name "unconnected-(IC6-(PCINT9{slash}OC1B)PC5-Pad25)") (class "Default")
      (node (ref "IC6") (pin "25") (pinfunction "(PCINT9/OC1B)PC5_25") (pintype "bidirectional"))
    )
    (net (code "164") (name "unconnected-(IC6-(RTS{slash}AIN5{slash}INT6)PD6-Pad12)") (class "Default")
      (node (ref "IC6") (pin "12") (pinfunction "(RTS/AIN5/INT6)PD6_12") (pintype "bidirectional"))
    )
    (net (code "165") (name "unconnected-(IC6-(SS{slash}PCINT0)PB0-Pad14)") (class "Default")
      (node (ref "IC6") (pin "14") (pinfunction "(SS/PCINT0)PB0_14") (pintype "bidirectional"))
    )
    (net (code "166") (name "unconnected-(IC6-(T1{slash}PCINT4)PB4-Pad18)") (class "Default")
      (node (ref "IC6") (pin "18") (pinfunction "(T1/PCINT4)PB4_18") (pintype "bidirectional"))
    )
    (net (code "167") (name "unconnected-(J3-ID-PadP4)") (class "Default")
      (node (ref "J3") (pin "P4") (pinfunction "ID_P4") (pintype "bidirectional"))
    )
    (net (code "168") (name "unconnected-(U1-NRST-Pad69)") (class "Default")
      (node (ref "U1") (pin "69") (pinfunction "NRST_69") (pintype "bidirectional"))
    )
    (net (code "169") (name "unconnected-(U1-PB22-Pad141)") (class "Default")
      (node (ref "U1") (pin "141") (pinfunction "PB22_141") (pintype "bidirectional"))
    )
    (net (code "170") (name "unconnected-(U1-PB24-Pad143)") (class "Default")
      (node (ref "U1") (pin "143") (pinfunction "PB24_143") (pintype "bidirectional"))
    )
    (net (code "171") (name "unconnected-(U1-PC0-Pad130)") (class "Default")
      (node (ref "U1") (pin "130") (pinfunction "PC0_130") (pintype "bidirectional"))
    )
    (net (code "172") (name "unconnected-(U1-PC10-Pad117)") (class "Default")
      (node (ref "U1") (pin "117") (pinfunction "PC10_117") (pintype "bidirectional"))
    )
    (net (code "173") (name "unconnected-(U1-PC11-Pad93)") (class "Default")
      (node (ref "U1") (pin "93") (pinfunction "PC11_93") (pintype "bidirectional"))
    )
    (net (code "174") (name "unconnected-(U1-PC20-Pad131)") (class "Default")
      (node (ref "U1") (pin "131") (pinfunction "PC20_131") (pintype "bidirectional"))
    )
    (net (code "175") (name "unconnected-(U1-PC27-Pad138)") (class "Default")
      (node (ref "U1") (pin "138") (pinfunction "PC27_138") (pintype "bidirectional"))
    )
    (net (code "176") (name "unconnected-(U1-SHDN-Pad50)") (class "Default")
      (node (ref "U1") (pin "50") (pinfunction "SHDN_50") (pintype "output"))
    )
  )
)
